# FlashMemorySchDoc.net
KiCad netlist of a schematic drawn in Altium Designer
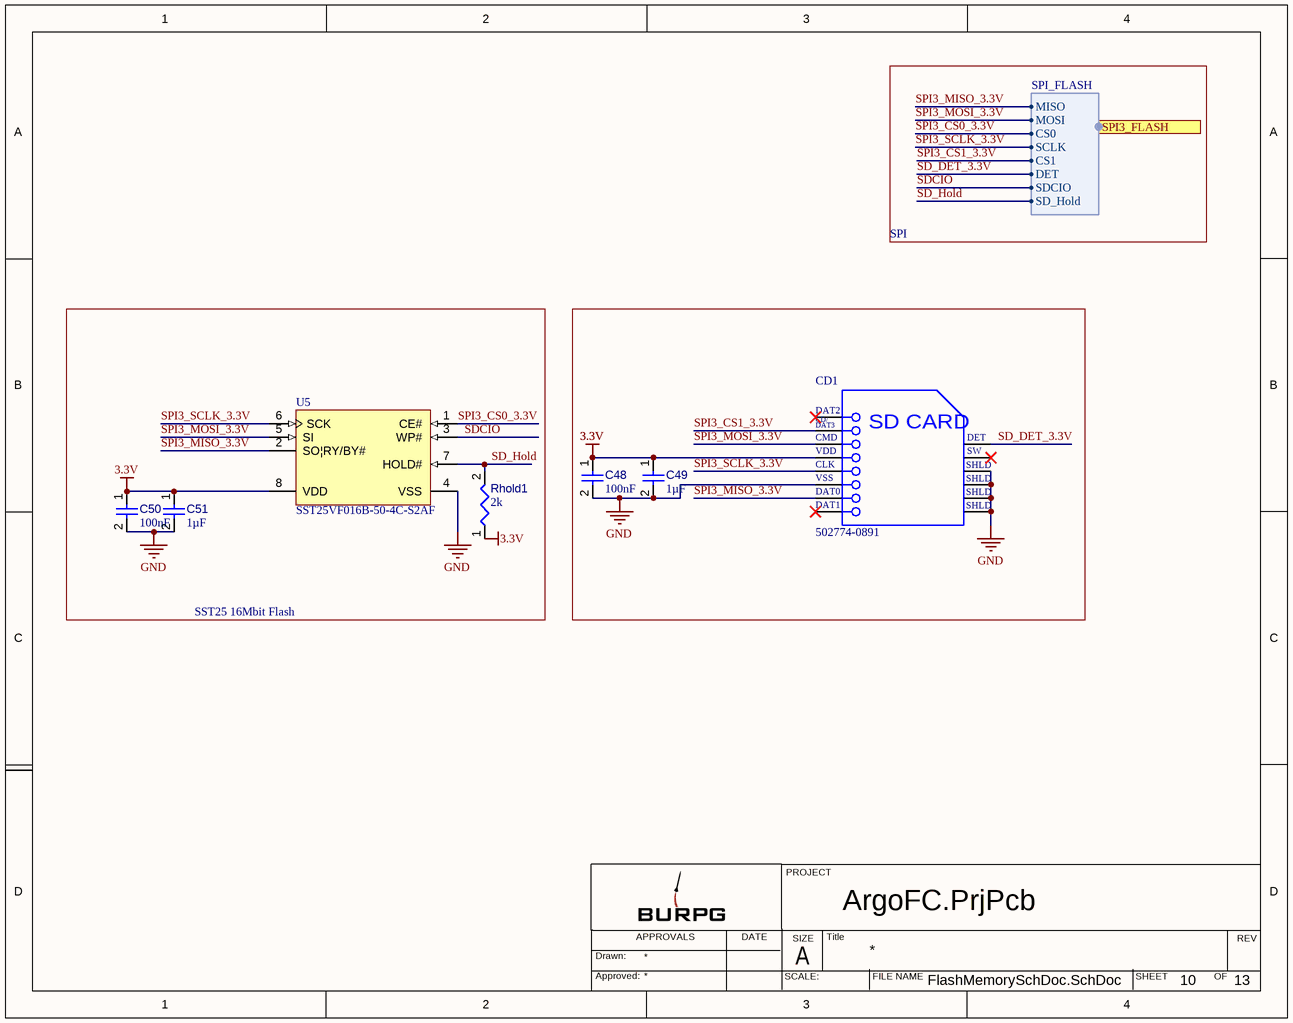
[diagram p0: FlashMemorySchDoc.SchDoc]

(export (version "E")
  (design (tool "Eeschema 10.0.6"))
  (components
    (comp (ref "C48")
      (value "100nF")
      (footprint "CAPC0402(1005)60_L")
      (description "Chip Capacitor, 100nF +/-20%, 25V, 0402, Thickness 0.6 mm")
      (fields (field (name "TOLERANCE") "10%") (field (name "Comment") "Capacitor 100nF +/-20% 25V 0402"))
      (libsource (lib "Gidon_Workspace") (part "CAP-NP-2"))
    )
    (comp (ref "C49")
      (value "1µF")
      (footprint "CAPC1608X94X35NL15T15")
      (description "Chip Capacitor, 1 uF, +/- 10%, 16 V, 0603 (1608 Metric)")
      (fields (field (name "TOLERANCE") "10%") (field (name "Comment") "Capacitor 1 uF +/- 10% 16 V 0603"))
      (libsource (lib "Gidon_Workspace") (part "CAP-NP-2"))
    )
    (comp (ref "C50")
      (value "100nF")
      (footprint "CAPC0402(1005)60_L")
      (description "Chip Capacitor, 100nF +/-20%, 25V, 0402, Thickness 0.6 mm")
      (fields (field (name "TOLERANCE") "10%") (field (name "Comment") "Capacitor 100nF +/-20% 25V 0402"))
      (libsource (lib "Gidon_Workspace") (part "CAP-NP-2"))
    )
    (comp (ref "C51")
      (value "1µF")
      (footprint "CAPC1608X94X35NL15T15")
      (description "Chip Capacitor, 1 uF, +/- 10%, 16 V, 0603 (1608 Metric)")
      (fields (field (name "TOLERANCE") "10%") (field (name "Comment") "Capacitor 1 uF +/- 10% 16 V 0603"))
      (libsource (lib "Gidon_Workspace") (part "CAP-NP-2"))
    )
    (comp (ref "CD1")
      (value "502774-0891")
      (footprint "MOLX-502774-0891_V")
      (description "Micro SD Memory Card Connector, 0.5 A, 10 V (DC), -25 to 85 degC, 8-Pin SMT, RoHS, Tape and Reel")
      (fields (field (name "MANUFACTURER") "Molex"))
      (libsource (lib "Altium Content Vault") (part "CN-SD-8-2SW-4S_B"))
    )
    (comp (ref "Rhold1")
      (value "2k")
      (footprint "RESC0402(1005)_L")
      (description "Chip Resistor, 2 kOhms, +/-5 %, 63 mW, -55 to 155 degC, 0402")
      (fields (field (name "TOLERANCE") "5%") (field (name "POWER") "63mW"))
      (libsource (lib "Yuxuan chen") (part "RES-2"))
    )
    (comp (ref "U5")
      (value "SST25VF016B-50-4C-S2AF")
      (footprint "MCHP-SOIC-S2A8_M")
      (description "16 Mbit SPI Serial Flash, 2.7 to 3.6 V, 50 MHz, 0 to 70 degC, 8-pin SOIC (S2A8), Tube")
      (fields (field (name "MANUFACTURER") "Microchip"))
      (libsource (lib "Altium Content Vault") (part "MCHP-SST25VFXXXB-SOIX-8"))
    )
  )
  (nets
    (net (code "2") (name "/SDCIO") (class "Default")
      (node (ref "U5") (pin "3") (pinfunction "WP#_3") (pintype "input"))
    )
    (net (code "3") (name "/SD_DET_3.3V") (class "Default")
      (node (ref "CD1") (pin "9") (pinfunction "DETECT_9") (pintype "passive"))
    )
    (net (code "4") (name "/SD_Hold") (class "Default")
      (node (ref "Rhold1") (pin "2") (pinfunction "2_2") (pintype "passive"))
      (node (ref "U5") (pin "7") (pinfunction "HOLD#_7") (pintype "input"))
    )
    (net (code "5") (name "/SPI3_CS0_3.3V") (class "Default")
      (node (ref "U5") (pin "1") (pinfunction "CE#_1") (pintype "input"))
    )
    (net (code "6") (name "/SPI3_CS1_3.3V") (class "Default")
      (node (ref "CD1") (pin "2") (pinfunction "CD/DAT3_2") (pintype "passive"))
    )
    (net (code "7") (name "/SPI3_MISO_3.3V") (class "Default")
      (node (ref "CD1") (pin "7") (pinfunction "DAT0_7") (pintype "passive"))
      (node (ref "U5") (pin "2") (pinfunction "SO¦RY/BY#_2") (pintype "tri_state"))
    )
    (net (code "8") (name "/SPI3_MOSI_3.3V") (class "Default")
      (node (ref "CD1") (pin "3") (pinfunction "CMD_3") (pintype "passive"))
      (node (ref "U5") (pin "5") (pinfunction "SI_5") (pintype "input"))
    )
    (net (code "9") (name "/SPI3_SCLK_3.3V") (class "Default")
      (node (ref "CD1") (pin "5") (pinfunction "CLK_5") (pintype "passive"))
      (node (ref "U5") (pin "6") (pinfunction "SCK_6") (pintype "input"))
    )
    (net (code "11") (name "3.3V") (class "Default")
      (node (ref "C48") (pin "1") (pinfunction "1_1") (pintype "passive"))
      (node (ref "C49") (pin "1") (pinfunction "1_1") (pintype "passive"))
      (node (ref "C50") (pin "1") (pinfunction "1_1") (pintype "passive"))
      (node (ref "C51") (pin "1") (pinfunction "1_1") (pintype "passive"))
      (node (ref "CD1") (pin "4") (pinfunction "VDD_4") (pintype "passive"))
      (node (ref "Rhold1") (pin "1") (pinfunction "1_1") (pintype "passive"))
      (node (ref "U5") (pin "8") (pinfunction "VDD_8") (pintype "power_in"))
    )
    (net (code "12") (name "GND") (class "Default")
      (node (ref "C48") (pin "2") (pinfunction "2_2") (pintype "passive"))
      (node (ref "C49") (pin "2") (pinfunction "2_2") (pintype "passive"))
      (node (ref "C50") (pin "2") (pinfunction "2_2") (pintype "passive"))
      (node (ref "C51") (pin "2") (pinfunction "2_2") (pintype "passive"))
      (node (ref "CD1") (pin "11") (pinfunction "SHLD_11") (pintype "passive"))
      (node (ref "CD1") (pin "12") (pinfunction "SHLD_12") (pintype "passive"))
      (node (ref "CD1") (pin "13") (pinfunction "SHLD_13") (pintype "passive"))
      (node (ref "CD1") (pin "14") (pinfunction "SHLD_14") (pintype "passive"))
      (node (ref "CD1") (pin "6") (pinfunction "VSS_6") (pintype "passive"))
      (node (ref "U5") (pin "4") (pinfunction "VSS_4") (pintype "power_in"))
    )
    (net (code "13") (name "unconnected-(CD1-DAT1-Pad8)") (class "Default")
      (node (ref "CD1") (pin "8") (pinfunction "DAT1_8") (pintype "passive+no_connect"))
    )
    (net (code "14") (name "unconnected-(CD1-DAT2-Pad1)") (class "Default")
      (node (ref "CD1") (pin "1") (pinfunction "DAT2_1") (pintype "passive+no_connect"))
    )
    (net (code "15") (name "unconnected-(CD1-SWITCH-Pad10)") (class "Default")
      (node (ref "CD1") (pin "10") (pinfunction "SWITCH_10") (pintype "passive+no_connect"))
    )
  )
)
